# 4_Reflective_Sensors.net
KiCad netlist of a schematic drawn in Altium Designer
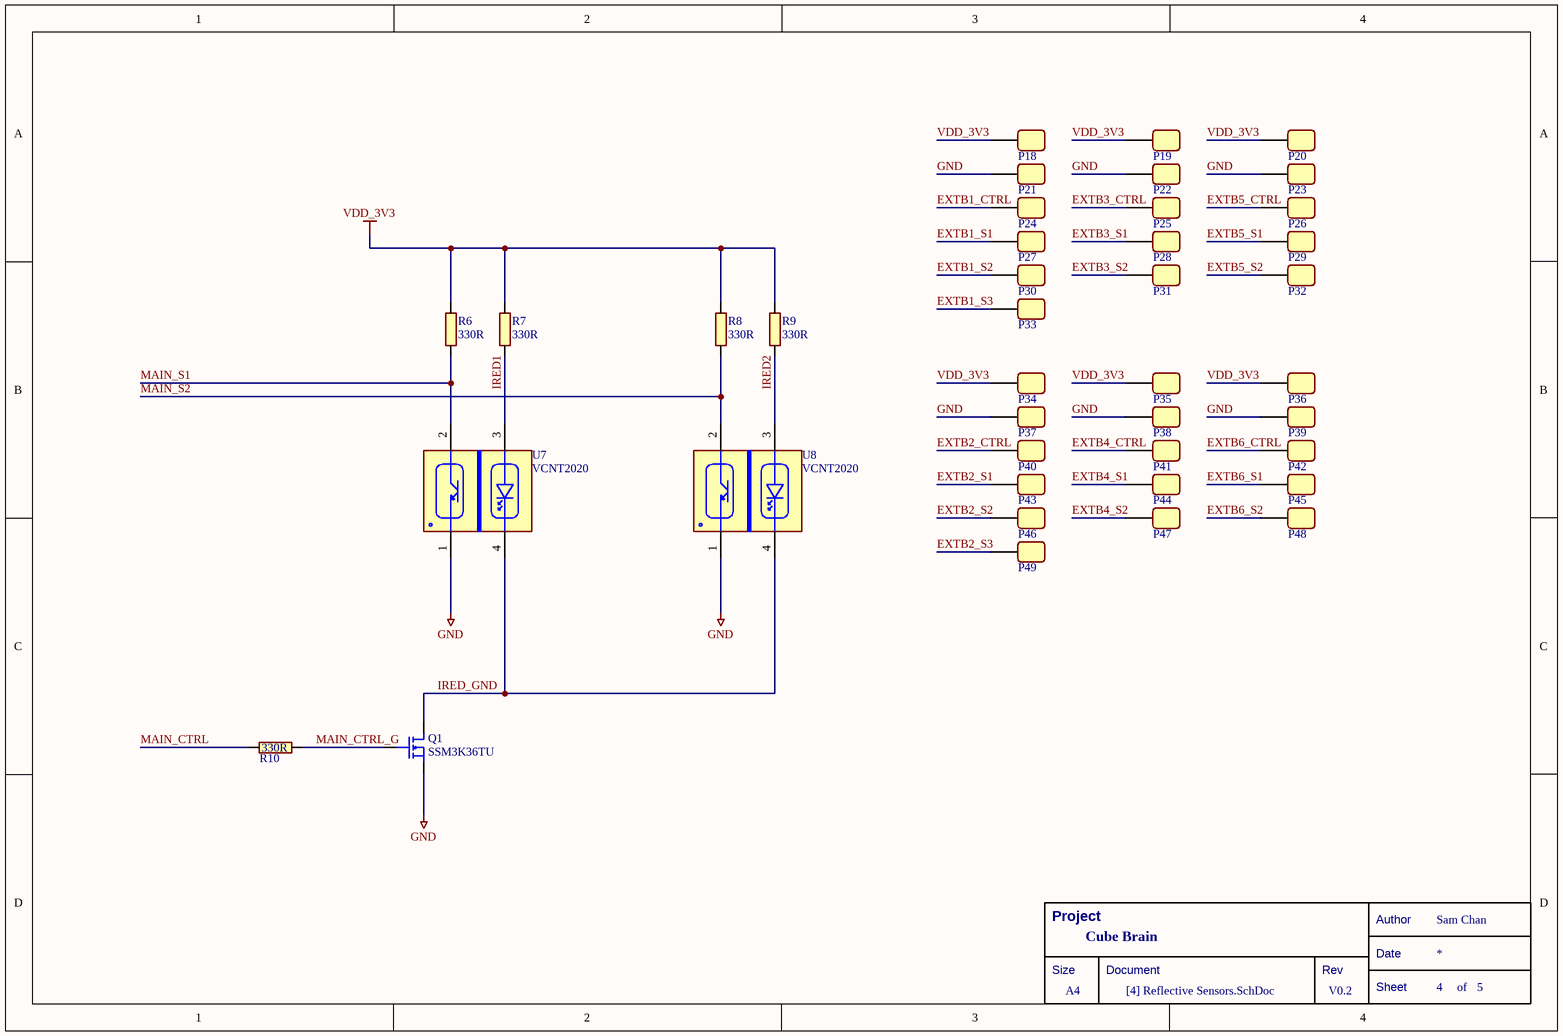
[diagram p0: [4] Reflective Sensors.SchDoc]

(export (version "E")
  (design (tool "Eeschema 10.0.6"))
  (components
    (comp (ref "P18")
      (value "PAD_4")
      (footprint "PAD_B2B")
      (description "a Pad for board to board connection")
      (libsource (lib "Cube Library") (part "PAD_4"))
    )
    (comp (ref "P19")
      (value "PAD_4")
      (footprint "PAD_B2B")
      (description "a Pad for board to board connection")
      (libsource (lib "Cube Library") (part "PAD_4"))
    )
    (comp (ref "P20")
      (value "PAD_4")
      (footprint "PAD_B2B")
      (description "a Pad for board to board connection")
      (libsource (lib "Cube Library") (part "PAD_4"))
    )
    (comp (ref "P21")
      (value "PAD_4")
      (footprint "PAD_B2B")
      (description "a Pad for board to board connection")
      (libsource (lib "Cube Library") (part "PAD_4"))
    )
    (comp (ref "P22")
      (value "PAD_4")
      (footprint "PAD_B2B")
      (description "a Pad for board to board connection")
      (libsource (lib "Cube Library") (part "PAD_4"))
    )
    (comp (ref "P23")
      (value "PAD_4")
      (footprint "PAD_B2B")
      (description "a Pad for board to board connection")
      (libsource (lib "Cube Library") (part "PAD_4"))
    )
    (comp (ref "P24")
      (value "PAD_4")
      (footprint "PAD_B2B")
      (description "a Pad for board to board connection")
      (libsource (lib "Cube Library") (part "PAD_4"))
    )
    (comp (ref "P25")
      (value "PAD_4")
      (footprint "PAD_B2B")
      (description "a Pad for board to board connection")
      (libsource (lib "Cube Library") (part "PAD_4"))
    )
    (comp (ref "P26")
      (value "PAD_4")
      (footprint "PAD_B2B")
      (description "a Pad for board to board connection")
      (libsource (lib "Cube Library") (part "PAD_4"))
    )
    (comp (ref "P27")
      (value "PAD_4")
      (footprint "PAD_B2B")
      (description "a Pad for board to board connection")
      (libsource (lib "Cube Library") (part "PAD_4"))
    )
    (comp (ref "P28")
      (value "PAD_4")
      (footprint "PAD_B2B")
      (description "a Pad for board to board connection")
      (libsource (lib "Cube Library") (part "PAD_4"))
    )
    (comp (ref "P29")
      (value "PAD_4")
      (footprint "PAD_B2B")
      (description "a Pad for board to board connection")
      (libsource (lib "Cube Library") (part "PAD_4"))
    )
    (comp (ref "P30")
      (value "PAD_4")
      (footprint "PAD_B2B")
      (description "a Pad for board to board connection")
      (libsource (lib "Cube Library") (part "PAD_4"))
    )
    (comp (ref "P31")
      (value "PAD_4")
      (footprint "PAD_B2B")
      (description "a Pad for board to board connection")
      (libsource (lib "Cube Library") (part "PAD_4"))
    )
    (comp (ref "P32")
      (value "PAD_4")
      (footprint "PAD_B2B")
      (description "a Pad for board to board connection")
      (libsource (lib "Cube Library") (part "PAD_4"))
    )
    (comp (ref "P33")
      (value "PAD_4")
      (footprint "PAD_B2B")
      (description "a Pad for board to board connection")
      (libsource (lib "Cube Library") (part "PAD_4"))
    )
    (comp (ref "P34")
      (value "PAD_4")
      (footprint "PAD_B2B")
      (description "a Pad for board to board connection")
      (libsource (lib "Cube Library") (part "PAD_4"))
    )
    (comp (ref "P35")
      (value "PAD_4")
      (footprint "PAD_B2B")
      (description "a Pad for board to board connection")
      (libsource (lib "Cube Library") (part "PAD_4"))
    )
    (comp (ref "P36")
      (value "PAD_4")
      (footprint "PAD_B2B")
      (description "a Pad for board to board connection")
      (libsource (lib "Cube Library") (part "PAD_4"))
    )
    (comp (ref "P37")
      (value "PAD_4")
      (footprint "PAD_B2B")
      (description "a Pad for board to board connection")
      (libsource (lib "Cube Library") (part "PAD_4"))
    )
    (comp (ref "P38")
      (value "PAD_4")
      (footprint "PAD_B2B")
      (description "a Pad for board to board connection")
      (libsource (lib "Cube Library") (part "PAD_4"))
    )
    (comp (ref "P39")
      (value "PAD_4")
      (footprint "PAD_B2B")
      (description "a Pad for board to board connection")
      (libsource (lib "Cube Library") (part "PAD_4"))
    )
    (comp (ref "P40")
      (value "PAD_4")
      (footprint "PAD_B2B")
      (description "a Pad for board to board connection")
      (libsource (lib "Cube Library") (part "PAD_4"))
    )
    (comp (ref "P41")
      (value "PAD_4")
      (footprint "PAD_B2B")
      (description "a Pad for board to board connection")
      (libsource (lib "Cube Library") (part "PAD_4"))
    )
    (comp (ref "P42")
      (value "PAD_4")
      (footprint "PAD_B2B")
      (description "a Pad for board to board connection")
      (libsource (lib "Cube Library") (part "PAD_4"))
    )
    (comp (ref "P43")
      (value "PAD_4")
      (footprint "PAD_B2B")
      (description "a Pad for board to board connection")
      (libsource (lib "Cube Library") (part "PAD_4"))
    )
    (comp (ref "P44")
      (value "PAD_4")
      (footprint "PAD_B2B")
      (description "a Pad for board to board connection")
      (libsource (lib "Cube Library") (part "PAD_4"))
    )
    (comp (ref "P45")
      (value "PAD_4")
      (footprint "PAD_B2B")
      (description "a Pad for board to board connection")
      (libsource (lib "Cube Library") (part "PAD_4"))
    )
    (comp (ref "P46")
      (value "PAD_4")
      (footprint "PAD_B2B")
      (description "a Pad for board to board connection")
      (libsource (lib "Cube Library") (part "PAD_4"))
    )
    (comp (ref "P47")
      (value "PAD_4")
      (footprint "PAD_B2B")
      (description "a Pad for board to board connection")
      (libsource (lib "Cube Library") (part "PAD_4"))
    )
    (comp (ref "P48")
      (value "PAD_4")
      (footprint "PAD_B2B")
      (description "a Pad for board to board connection")
      (libsource (lib "Cube Library") (part "PAD_4"))
    )
    (comp (ref "P49")
      (value "PAD_4")
      (footprint "PAD_B2B")
      (description "a Pad for board to board connection")
      (libsource (lib "Cube Library") (part "PAD_4"))
    )
    (comp (ref "Q1")
      (value "SSM3K36TU")
      (footprint "SSM3K36TU")
      (description "N-Channel 20V 500mA (Ta) 800mW (Ta) Surface Mount UFM")
      (fields (field (name "MANUFACTURER") "Toshiba Semiconductor and Storage"))
      (libsource (lib "Cube Library") (part "SSM3K36TU"))
    )
    (comp (ref "R6")
      (value "330R")
      (footprint "RESC0402X04N")
      (description "RES SMD 330R OHM 1% 1/16W 0402")
      (fields
        (field (name "MANUFACTURER") "YAGEO")
        (field (name "MANUFACTURER PART NUMBER") "RC0402FR-07330RL")
        (field (name "RESISTANCE") "330R")
      )
      (libsource (lib "Cube Library") (part "RES 330R"))
    )
    (comp (ref "R7")
      (value "330R")
      (footprint "RESC0402X04N")
      (description "RES SMD 330R OHM 1% 1/16W 0402")
      (fields
        (field (name "MANUFACTURER") "YAGEO")
        (field (name "MANUFACTURER PART NUMBER") "RC0402FR-07330RL")
        (field (name "RESISTANCE") "330R")
      )
      (libsource (lib "Cube Library") (part "RES 330R"))
    )
    (comp (ref "R8")
      (value "330R")
      (footprint "RESC0402X04N")
      (description "RES SMD 330R OHM 1% 1/16W 0402")
      (fields
        (field (name "MANUFACTURER") "YAGEO")
        (field (name "MANUFACTURER PART NUMBER") "RC0402FR-07330RL")
        (field (name "RESISTANCE") "330R")
      )
      (libsource (lib "Cube Library") (part "RES 330R"))
    )
    (comp (ref "R9")
      (value "330R")
      (footprint "RESC0402X04N")
      (description "RES SMD 330R OHM 1% 1/16W 0402")
      (fields
        (field (name "MANUFACTURER") "YAGEO")
        (field (name "MANUFACTURER PART NUMBER") "RC0402FR-07330RL")
        (field (name "RESISTANCE") "330R")
      )
      (libsource (lib "Cube Library") (part "RES 330R"))
    )
    (comp (ref "R10")
      (value "330R")
      (footprint "RESC0402X04N")
      (description "RES SMD 330R OHM 1% 1/16W 0402")
      (fields
        (field (name "MANUFACTURER") "YAGEO")
        (field (name "MANUFACTURER PART NUMBER") "RC0402FR-07330RL")
        (field (name "RESISTANCE") "330R")
      )
      (libsource (lib "") (part "RES 330R_1"))
    )
    (comp (ref "U7")
      (value "VCNT2020")
      (footprint "VCNT2020")
      (description "REFLECTIVE SENSOR WITH PTR OUTPU")
      (fields (field (name "MANUFACTURER") "Vishay Semiconductor Opto Division"))
      (libsource (lib "Cube Library") (part "VCNT2020"))
    )
    (comp (ref "U8")
      (value "VCNT2020")
      (footprint "VCNT2020")
      (description "REFLECTIVE SENSOR WITH PTR OUTPU")
      (fields (field (name "MANUFACTURER") "Vishay Semiconductor Opto Division"))
      (libsource (lib "Cube Library") (part "VCNT2020"))
    )
  )
  (nets
    (net (code "1") (name "/EXTB1_CTRL") (class "Default")
      (node (ref "P24") (pin "1") (pinfunction "1_1") (pintype "passive"))
    )
    (net (code "2") (name "/EXTB1_S1") (class "Default")
      (node (ref "P27") (pin "1") (pinfunction "1_1") (pintype "passive"))
    )
    (net (code "3") (name "/EXTB1_S2") (class "Default")
      (node (ref "P30") (pin "1") (pinfunction "1_1") (pintype "passive"))
    )
    (net (code "4") (name "/EXTB1_S3") (class "Default")
      (node (ref "P33") (pin "1") (pinfunction "1_1") (pintype "passive"))
    )
    (net (code "5") (name "/EXTB2_CTRL") (class "Default")
      (node (ref "P40") (pin "1") (pinfunction "1_1") (pintype "passive"))
    )
    (net (code "6") (name "/EXTB2_S1") (class "Default")
      (node (ref "P43") (pin "1") (pinfunction "1_1") (pintype "passive"))
    )
    (net (code "7") (name "/EXTB2_S2") (class "Default")
      (node (ref "P46") (pin "1") (pinfunction "1_1") (pintype "passive"))
    )
    (net (code "8") (name "/EXTB2_S3") (class "Default")
      (node (ref "P49") (pin "1") (pinfunction "1_1") (pintype "passive"))
    )
    (net (code "9") (name "/EXTB3_CTRL") (class "Default")
      (node (ref "P25") (pin "1") (pinfunction "1_1") (pintype "passive"))
    )
    (net (code "10") (name "/EXTB3_S1") (class "Default")
      (node (ref "P28") (pin "1") (pinfunction "1_1") (pintype "passive"))
    )
    (net (code "11") (name "/EXTB3_S2") (class "Default")
      (node (ref "P31") (pin "1") (pinfunction "1_1") (pintype "passive"))
    )
    (net (code "12") (name "/EXTB4_CTRL") (class "Default")
      (node (ref "P41") (pin "1") (pinfunction "1_1") (pintype "passive"))
    )
    (net (code "13") (name "/EXTB4_S1") (class "Default")
      (node (ref "P44") (pin "1") (pinfunction "1_1") (pintype "passive"))
    )
    (net (code "14") (name "/EXTB4_S2") (class "Default")
      (node (ref "P47") (pin "1") (pinfunction "1_1") (pintype "passive"))
    )
    (net (code "15") (name "/EXTB5_CTRL") (class "Default")
      (node (ref "P26") (pin "1") (pinfunction "1_1") (pintype "passive"))
    )
    (net (code "16") (name "/EXTB5_S1") (class "Default")
      (node (ref "P29") (pin "1") (pinfunction "1_1") (pintype "passive"))
    )
    (net (code "17") (name "/EXTB5_S2") (class "Default")
      (node (ref "P32") (pin "1") (pinfunction "1_1") (pintype "passive"))
    )
    (net (code "18") (name "/EXTB6_CTRL") (class "Default")
      (node (ref "P42") (pin "1") (pinfunction "1_1") (pintype "passive"))
    )
    (net (code "19") (name "/EXTB6_S1") (class "Default")
      (node (ref "P45") (pin "1") (pinfunction "1_1") (pintype "passive"))
    )
    (net (code "20") (name "/EXTB6_S2") (class "Default")
      (node (ref "P48") (pin "1") (pinfunction "1_1") (pintype "passive"))
    )
    (net (code "21") (name "/IRED1") (class "Default")
      (node (ref "R7") (pin "1") (pinfunction "1_1") (pintype "passive"))
      (node (ref "U7") (pin "3") (pinfunction "3_3") (pintype "passive"))
    )
    (net (code "22") (name "/IRED2") (class "Default")
      (node (ref "R9") (pin "1") (pinfunction "1_1") (pintype "passive"))
      (node (ref "U8") (pin "3") (pinfunction "3_3") (pintype "passive"))
    )
    (net (code "23") (name "/IRED_GND") (class "Default")
      (node (ref "Q1") (pin "3") (pinfunction "3_3") (pintype "passive"))
      (node (ref "U7") (pin "4") (pinfunction "4_4") (pintype "passive"))
      (node (ref "U8") (pin "4") (pinfunction "4_4") (pintype "passive"))
    )
    (net (code "24") (name "/MAIN_CTRL") (class "Default")
      (node (ref "R10") (pin "2") (pinfunction "2_2") (pintype "passive"))
    )
    (net (code "25") (name "/MAIN_CTRL_G") (class "Default")
      (node (ref "Q1") (pin "1") (pinfunction "1_1") (pintype "passive"))
      (node (ref "R10") (pin "1") (pinfunction "1_1") (pintype "passive"))
    )
    (net (code "26") (name "/MAIN_S1") (class "Default")
      (node (ref "R6") (pin "1") (pinfunction "1_1") (pintype "passive"))
      (node (ref "U7") (pin "2") (pinfunction "2_2") (pintype "passive"))
    )
    (net (code "27") (name "/MAIN_S2") (class "Default")
      (node (ref "R8") (pin "1") (pinfunction "1_1") (pintype "passive"))
      (node (ref "U8") (pin "2") (pinfunction "2_2") (pintype "passive"))
    )
    (net (code "28") (name "GND") (class "Default")
      (node (ref "P21") (pin "1") (pinfunction "1_1") (pintype "passive"))
      (node (ref "P22") (pin "1") (pinfunction "1_1") (pintype "passive"))
      (node (ref "P23") (pin "1") (pinfunction "1_1") (pintype "passive"))
      (node (ref "P37") (pin "1") (pinfunction "1_1") (pintype "passive"))
      (node (ref "P38") (pin "1") (pinfunction "1_1") (pintype "passive"))
      (node (ref "P39") (pin "1") (pinfunction "1_1") (pintype "passive"))
      (node (ref "Q1") (pin "2") (pinfunction "2_2") (pintype "passive"))
      (node (ref "U7") (pin "1") (pinfunction "1_1") (pintype "passive"))
      (node (ref "U8") (pin "1") (pinfunction "1_1") (pintype "passive"))
    )
    (net (code "29") (name "VDD_3V3") (class "Default")
      (node (ref "P18") (pin "1") (pinfunction "1_1") (pintype "passive"))
      (node (ref "P19") (pin "1") (pinfunction "1_1") (pintype "passive"))
      (node (ref "P20") (pin "1") (pinfunction "1_1") (pintype "passive"))
      (node (ref "P34") (pin "1") (pinfunction "1_1") (pintype "passive"))
      (node (ref "P35") (pin "1") (pinfunction "1_1") (pintype "passive"))
      (node (ref "P36") (pin "1") (pinfunction "1_1") (pintype "passive"))
      (node (ref "R6") (pin "2") (pinfunction "2_2") (pintype "passive"))
      (node (ref "R7") (pin "2") (pinfunction "2_2") (pintype "passive"))
      (node (ref "R8") (pin "2") (pinfunction "2_2") (pintype "passive"))
      (node (ref "R9") (pin "2") (pinfunction "2_2") (pintype "passive"))
    )
  )
)
